# FlowRateSensor1.net
KiCad netlist of a schematic drawn in Altium Designer
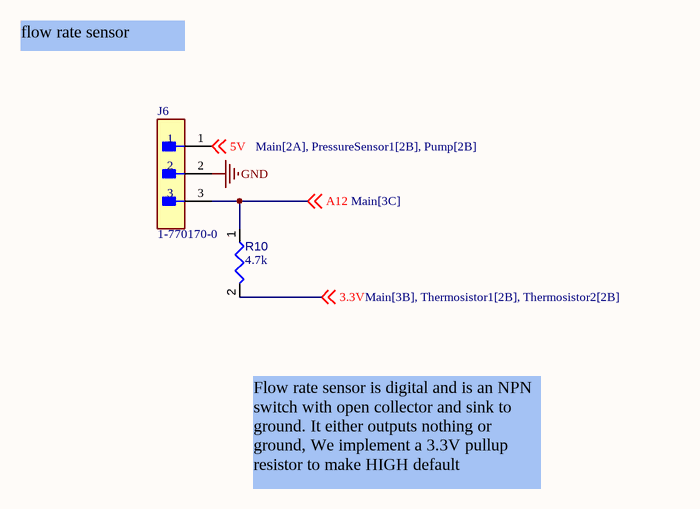
[diagram p0: FlowRateSensor1.SchDoc]

(export (version "E")
  (design (tool "Eeschema 10.0.6"))
  (components
    (comp (ref "J6")
      (value "1-770170-0")
      (footprint "FP-1-770170-0-MFG")
      (description "CONN HEADER VERT 3POS 4.14MM")
      (fields
        (field (name "OCTOPART") "https://octopart.com/1-770170-0-te+connectivity-46505214")
        (field (name "MANUFACTURER") "TE Connectivity")
      )
      (libsource (lib "Altium Content Vault") (part "0d3f023dd272f625e17a2be33dea85f"))
    )
    (comp (ref "R10")
      (value "4.7k")
      (footprint "RESC1005X40X25ML05T05")
      (description "Chip Resistor, 4.7 KOhm, +/- 1%, 0.1 W, -55 to 155 degC, 0402 (1005 Metric)")
      (fields (field (name "POWER") "100mW") (field (name "TOLERANCE") "1%"))
      (libsource (lib "Alt_ium Course") (part "RES-2"))
    )
  )
  (nets
    (net (code "1") (name "3.3V") (class "Default")
      (node (ref "R10") (pin "2") (pinfunction "2_2") (pintype "passive"))
    )
    (net (code "2") (name "5V") (class "Default")
      (node (ref "J6") (pin "1") (pinfunction "1_1") (pintype "passive"))
    )
    (net (code "3") (name "A12") (class "Default")
      (node (ref "J6") (pin "3") (pinfunction "3_3") (pintype "passive"))
      (node (ref "R10") (pin "1") (pinfunction "1_1") (pintype "passive"))
    )
    (net (code "4") (name "GND") (class "Default")
      (node (ref "J6") (pin "2") (pinfunction "2_2") (pintype "passive"))
    )
  )
)
